# wheel-opto-sensor.net
KiCad netlist of a schematic drawn in EAGLE
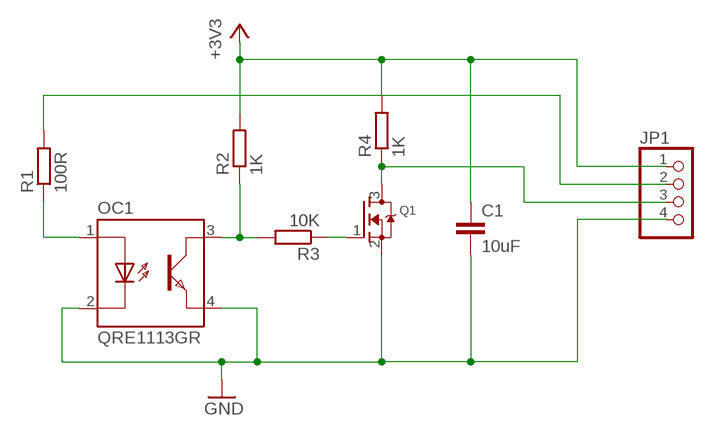
[diagram p0: schematic, sheet 1]

(export (version "E")
  (design (tool "Eeschema 10.0.6"))
  (components
    (comp (ref "C1")
      (value "10uF")
      (footprint "eagle-import:C1206")
      (libsource (lib "eagle-import") (part "C-EUC1206"))
    )
    (comp (ref "JP1")
      (value "PINHD-1X4")
      (footprint "eagle-import:1X04")
      (libsource (lib "eagle-import") (part "PINHD-1X4"))
    )
    (comp (ref "OC1")
      (value "QRE1113GR")
      (footprint "eagle-import:SMT_GULLWING_4")
      (libsource (lib "eagle-import") (part "QRE1113GR"))
    )
    (comp (ref "Q1")
      (value "MOSFET-NREFLOW")
      (footprint "eagle-import:SOT23")
      (libsource (lib "eagle-import") (part "MOSFET-NREFLOW"))
    )
    (comp (ref "R1")
      (value "100R")
      (footprint "eagle-import:M0805")
      (libsource (lib "eagle-import") (part "R-EU_M0805"))
    )
    (comp (ref "R2")
      (value "1K")
      (footprint "eagle-import:M0805")
      (libsource (lib "eagle-import") (part "R-EU_M0805"))
    )
    (comp (ref "R3")
      (value "10K")
      (footprint "eagle-import:M0805")
      (libsource (lib "eagle-import") (part "R-EU_M0805"))
    )
    (comp (ref "R4")
      (value "1K")
      (footprint "eagle-import:M0805")
      (libsource (lib "eagle-import") (part "R-EU_M0805"))
    )
  )
  (nets
    (net (code "1") (name "+3V3") (class "Default")
      (node (ref "C1") (pin "1") (pinfunction "1_1") (pintype "passive"))
      (node (ref "JP1") (pin "1") (pinfunction "1_1") (pintype "passive"))
      (node (ref "R2") (pin "2") (pinfunction "2_2") (pintype "passive"))
      (node (ref "R4") (pin "2") (pinfunction "2_2") (pintype "passive"))
    )
    (net (code "2") (name "GND") (class "Default")
      (node (ref "C1") (pin "2") (pinfunction "2_2") (pintype "passive"))
      (node (ref "JP1") (pin "4") (pinfunction "4_4") (pintype "passive"))
      (node (ref "OC1") (pin "2") (pinfunction "C_2") (pintype "bidirectional"))
      (node (ref "OC1") (pin "4") (pinfunction "TE_4") (pintype "bidirectional"))
      (node (ref "Q1") (pin "2") (pinfunction "S_2") (pintype "bidirectional"))
    )
    (net (code "3") (name "Net-(JP1-Pad2)") (class "Default")
      (node (ref "JP1") (pin "2") (pinfunction "2_2") (pintype "passive"))
      (node (ref "R1") (pin "2") (pinfunction "2_2") (pintype "passive"))
    )
    (net (code "4") (name "Net-(OC1-A)") (class "Default")
      (node (ref "OC1") (pin "1") (pinfunction "A_1") (pintype "bidirectional"))
      (node (ref "R1") (pin "1") (pinfunction "1_1") (pintype "passive"))
    )
    (net (code "5") (name "Net-(OC1-TC)") (class "Default")
      (node (ref "OC1") (pin "3") (pinfunction "TC_3") (pintype "bidirectional"))
      (node (ref "R2") (pin "1") (pinfunction "1_1") (pintype "passive"))
      (node (ref "R3") (pin "2") (pinfunction "2_2") (pintype "passive"))
    )
    (net (code "6") (name "Net-(Q1-D)") (class "Default")
      (node (ref "JP1") (pin "3") (pinfunction "3_3") (pintype "passive"))
      (node (ref "Q1") (pin "3") (pinfunction "D_3") (pintype "bidirectional"))
      (node (ref "R4") (pin "1") (pinfunction "1_1") (pintype "passive"))
    )
    (net (code "7") (name "Net-(Q1-G)") (class "Default")
      (node (ref "Q1") (pin "1") (pinfunction "G_1") (pintype "bidirectional"))
      (node (ref "R3") (pin "1") (pinfunction "1_1") (pintype "passive"))
    )
  )
)
